# tasiyiciyolsuz.net
KiCad netlist of a schematic drawn in EAGLE
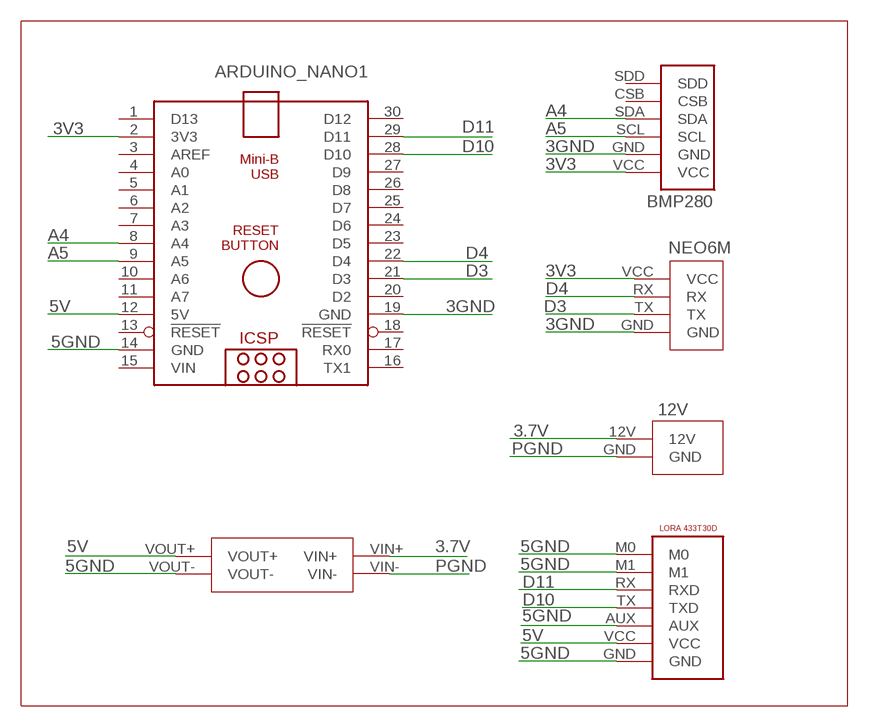
[diagram p0: schematic, sheet 1]

(export (version "E")
  (design (tool "Eeschema 10.0.6"))
  (components
    (comp (ref "ARDUINO_NANO1")
      (value "ARDUINO_NANO")
      (footprint "eagle-import:ARDUINO_NANO")
      (libsource (lib "eagle-import") (part "ARDUINO_NANO"))
    )
    (comp (ref "BMP1")
      (value "BMP280")
      (footprint "eagle-import:BMP280")
      (libsource (lib "eagle-import") (part "BMP280"))
    )
    (comp (ref "U$1")
      (value "12V")
      (footprint "eagle-import:12V")
      (libsource (lib "eagle-import") (part "12V"))
    )
    (comp (ref "U$2")
      (value "LORAFULLSIZE")
      (footprint "eagle-import:LORAFULLSIZE")
      (libsource (lib "eagle-import") (part "LORAFULLSIZE"))
    )
    (comp (ref "U$3")
      (value "MT3608_REGULATOR")
      (footprint "eagle-import:MT3608_REGULATOR")
      (libsource (lib "eagle-import") (part "MT3608_REGULATOR"))
    )
    (comp (ref "U$4")
      (value "NEO6M")
      (footprint "eagle-import:NEO6M")
      (libsource (lib "eagle-import") (part "NEO6M"))
    )
  )
  (nets
    (net (code "1") (name "/3.7V") (class "Default")
      (node (ref "U$1") (pin "12V") (pinfunction "12V_12V") (pintype "bidirectional"))
      (node (ref "U$3") (pin "VIN+") (pinfunction "VIN+_VIN+") (pintype "bidirectional"))
    )
    (net (code "2") (name "/3GND") (class "Default")
      (node (ref "ARDUINO_NANO1") (pin "19") (pinfunction "GND_19") (pintype "power_in"))
      (node (ref "BMP1") (pin "GND") (pinfunction "GND_GND") (pintype "bidirectional"))
      (node (ref "U$4") (pin "GND") (pinfunction "GND_GND") (pintype "bidirectional"))
    )
    (net (code "3") (name "/3V3") (class "Default")
      (node (ref "ARDUINO_NANO1") (pin "2") (pinfunction "3V3_2") (pintype "output"))
      (node (ref "BMP1") (pin "VCC") (pinfunction "VCC_VCC") (pintype "bidirectional"))
      (node (ref "U$4") (pin "VCC") (pinfunction "VCC_VCC") (pintype "bidirectional"))
    )
    (net (code "4") (name "/5GND") (class "Default")
      (node (ref "ARDUINO_NANO1") (pin "14") (pinfunction "GND_14") (pintype "power_in"))
      (node (ref "U$2") (pin "AUX") (pinfunction "AUX_AUX") (pintype "bidirectional"))
      (node (ref "U$2") (pin "GND") (pinfunction "GND_GND") (pintype "bidirectional"))
      (node (ref "U$2") (pin "M0") (pinfunction "M0_M0") (pintype "bidirectional"))
      (node (ref "U$2") (pin "M1") (pinfunction "M1_M1") (pintype "bidirectional"))
      (node (ref "U$3") (pin "VOUT-") (pinfunction "VOUT-_VOUT-") (pintype "bidirectional"))
    )
    (net (code "5") (name "/5V") (class "Default")
      (node (ref "ARDUINO_NANO1") (pin "12") (pinfunction "5V_12") (pintype "power_in"))
      (node (ref "U$2") (pin "VCC") (pinfunction "VCC_VCC") (pintype "bidirectional"))
      (node (ref "U$3") (pin "VOUT+") (pinfunction "VOUT+_VOUT+") (pintype "bidirectional"))
    )
    (net (code "6") (name "/A4") (class "Default")
      (node (ref "ARDUINO_NANO1") (pin "8") (pinfunction "A4_8") (pintype "bidirectional"))
      (node (ref "BMP1") (pin "SDA") (pinfunction "SDA_SDA") (pintype "bidirectional"))
    )
    (net (code "7") (name "/A5") (class "Default")
      (node (ref "ARDUINO_NANO1") (pin "9") (pinfunction "A5_9") (pintype "bidirectional"))
      (node (ref "BMP1") (pin "SCL") (pinfunction "SCL_SCL") (pintype "bidirectional"))
    )
    (net (code "8") (name "/D3") (class "Default")
      (node (ref "ARDUINO_NANO1") (pin "21") (pinfunction "D3_21") (pintype "bidirectional"))
      (node (ref "U$4") (pin "TX") (pinfunction "TX_TX") (pintype "bidirectional"))
    )
    (net (code "9") (name "/D4") (class "Default")
      (node (ref "ARDUINO_NANO1") (pin "22") (pinfunction "D4_22") (pintype "bidirectional"))
      (node (ref "U$4") (pin "RX") (pinfunction "RX_RX") (pintype "bidirectional"))
    )
    (net (code "10") (name "/D10") (class "Default")
      (node (ref "ARDUINO_NANO1") (pin "28") (pinfunction "D10_28") (pintype "bidirectional"))
      (node (ref "U$2") (pin "TX") (pinfunction "TXD_TX") (pintype "bidirectional"))
    )
    (net (code "11") (name "/D11") (class "Default")
      (node (ref "ARDUINO_NANO1") (pin "29") (pinfunction "D11_29") (pintype "bidirectional"))
      (node (ref "U$2") (pin "RX") (pinfunction "RXD_RX") (pintype "bidirectional"))
    )
    (net (code "12") (name "/PGND") (class "Default")
      (node (ref "U$1") (pin "GND") (pinfunction "GND_GND") (pintype "bidirectional"))
      (node (ref "U$3") (pin "VIN-") (pinfunction "VIN-_VIN-") (pintype "bidirectional"))
    )
    (net (code "13") (name "/VIN") (class "Default")
      (node (ref "ARDUINO_NANO1") (pin "15") (pinfunction "VIN_15") (pintype "power_in"))
    )
    (net (code "14") (name "unconnected-(ARDUINO_NANO1-A0-Pad4)") (class "Default")
      (node (ref "ARDUINO_NANO1") (pin "4") (pinfunction "A0_4") (pintype "bidirectional"))
    )
    (net (code "15") (name "unconnected-(ARDUINO_NANO1-A1-Pad5)") (class "Default")
      (node (ref "ARDUINO_NANO1") (pin "5") (pinfunction "A1_5") (pintype "bidirectional"))
    )
    (net (code "16") (name "unconnected-(ARDUINO_NANO1-A2-Pad6)") (class "Default")
      (node (ref "ARDUINO_NANO1") (pin "6") (pinfunction "A2_6") (pintype "bidirectional"))
    )
    (net (code "17") (name "unconnected-(ARDUINO_NANO1-A3-Pad7)") (class "Default")
      (node (ref "ARDUINO_NANO1") (pin "7") (pinfunction "A3_7") (pintype "bidirectional"))
    )
    (net (code "18") (name "unconnected-(ARDUINO_NANO1-A6-Pad10)") (class "Default")
      (node (ref "ARDUINO_NANO1") (pin "10") (pinfunction "A6_10") (pintype "bidirectional"))
    )
    (net (code "19") (name "unconnected-(ARDUINO_NANO1-A7-Pad11)") (class "Default")
      (node (ref "ARDUINO_NANO1") (pin "11") (pinfunction "A7_11") (pintype "bidirectional"))
    )
    (net (code "20") (name "unconnected-(ARDUINO_NANO1-AREF-Pad3)") (class "Default")
      (node (ref "ARDUINO_NANO1") (pin "3") (pinfunction "AREF_3") (pintype "input"))
    )
    (net (code "21") (name "unconnected-(ARDUINO_NANO1-D2-Pad20)") (class "Default")
      (node (ref "ARDUINO_NANO1") (pin "20") (pinfunction "D2_20") (pintype "bidirectional"))
    )
    (net (code "22") (name "unconnected-(ARDUINO_NANO1-D5-Pad23)") (class "Default")
      (node (ref "ARDUINO_NANO1") (pin "23") (pinfunction "D5_23") (pintype "bidirectional"))
    )
    (net (code "23") (name "unconnected-(ARDUINO_NANO1-D6-Pad24)") (class "Default")
      (node (ref "ARDUINO_NANO1") (pin "24") (pinfunction "D6_24") (pintype "bidirectional"))
    )
    (net (code "24") (name "unconnected-(ARDUINO_NANO1-D7-Pad25)") (class "Default")
      (node (ref "ARDUINO_NANO1") (pin "25") (pinfunction "D7_25") (pintype "bidirectional"))
    )
    (net (code "25") (name "unconnected-(ARDUINO_NANO1-D8-Pad26)") (class "Default")
      (node (ref "ARDUINO_NANO1") (pin "26") (pinfunction "D8_26") (pintype "bidirectional"))
    )
    (net (code "26") (name "unconnected-(ARDUINO_NANO1-D9-Pad27)") (class "Default")
      (node (ref "ARDUINO_NANO1") (pin "27") (pinfunction "D9_27") (pintype "bidirectional"))
    )
    (net (code "27") (name "unconnected-(ARDUINO_NANO1-D12-Pad30)") (class "Default")
      (node (ref "ARDUINO_NANO1") (pin "30") (pinfunction "D12_30") (pintype "bidirectional"))
    )
    (net (code "28") (name "unconnected-(ARDUINO_NANO1-D13-Pad1)") (class "Default")
      (node (ref "ARDUINO_NANO1") (pin "1") (pinfunction "D13_1") (pintype "bidirectional"))
    )
    (net (code "29") (name "unconnected-(ARDUINO_NANO1-RX0-Pad17)") (class "Default")
      (node (ref "ARDUINO_NANO1") (pin "17") (pinfunction "RX0_17") (pintype "bidirectional"))
    )
    (net (code "30") (name "unconnected-(ARDUINO_NANO1-TX1-Pad16)") (class "Default")
      (node (ref "ARDUINO_NANO1") (pin "16") (pinfunction "TX1_16") (pintype "bidirectional"))
    )
    (net (code "31") (name "unconnected-(ARDUINO_NANO1-~{RESET}-Pad13)") (class "Default")
      (node (ref "ARDUINO_NANO1") (pin "13") (pinfunction "~{RESET}_13") (pintype "input"))
    )
    (net (code "32") (name "unconnected-(ARDUINO_NANO1-~{RESET}-Pad18)") (class "Default")
      (node (ref "ARDUINO_NANO1") (pin "18") (pinfunction "~{RESET}_18") (pintype "input"))
    )
    (net (code "33") (name "unconnected-(BMP1-PadCSB)") (class "Default")
      (node (ref "BMP1") (pin "CSB") (pinfunction "CSB_CSB") (pintype "bidirectional"))
    )
    (net (code "34") (name "unconnected-(BMP1-PadSDD)") (class "Default")
      (node (ref "BMP1") (pin "SDD") (pinfunction "SDD_SDD") (pintype "bidirectional"))
    )
  )
)
